# Microcontroller.net
KiCad netlist of a schematic drawn in Altium Designer
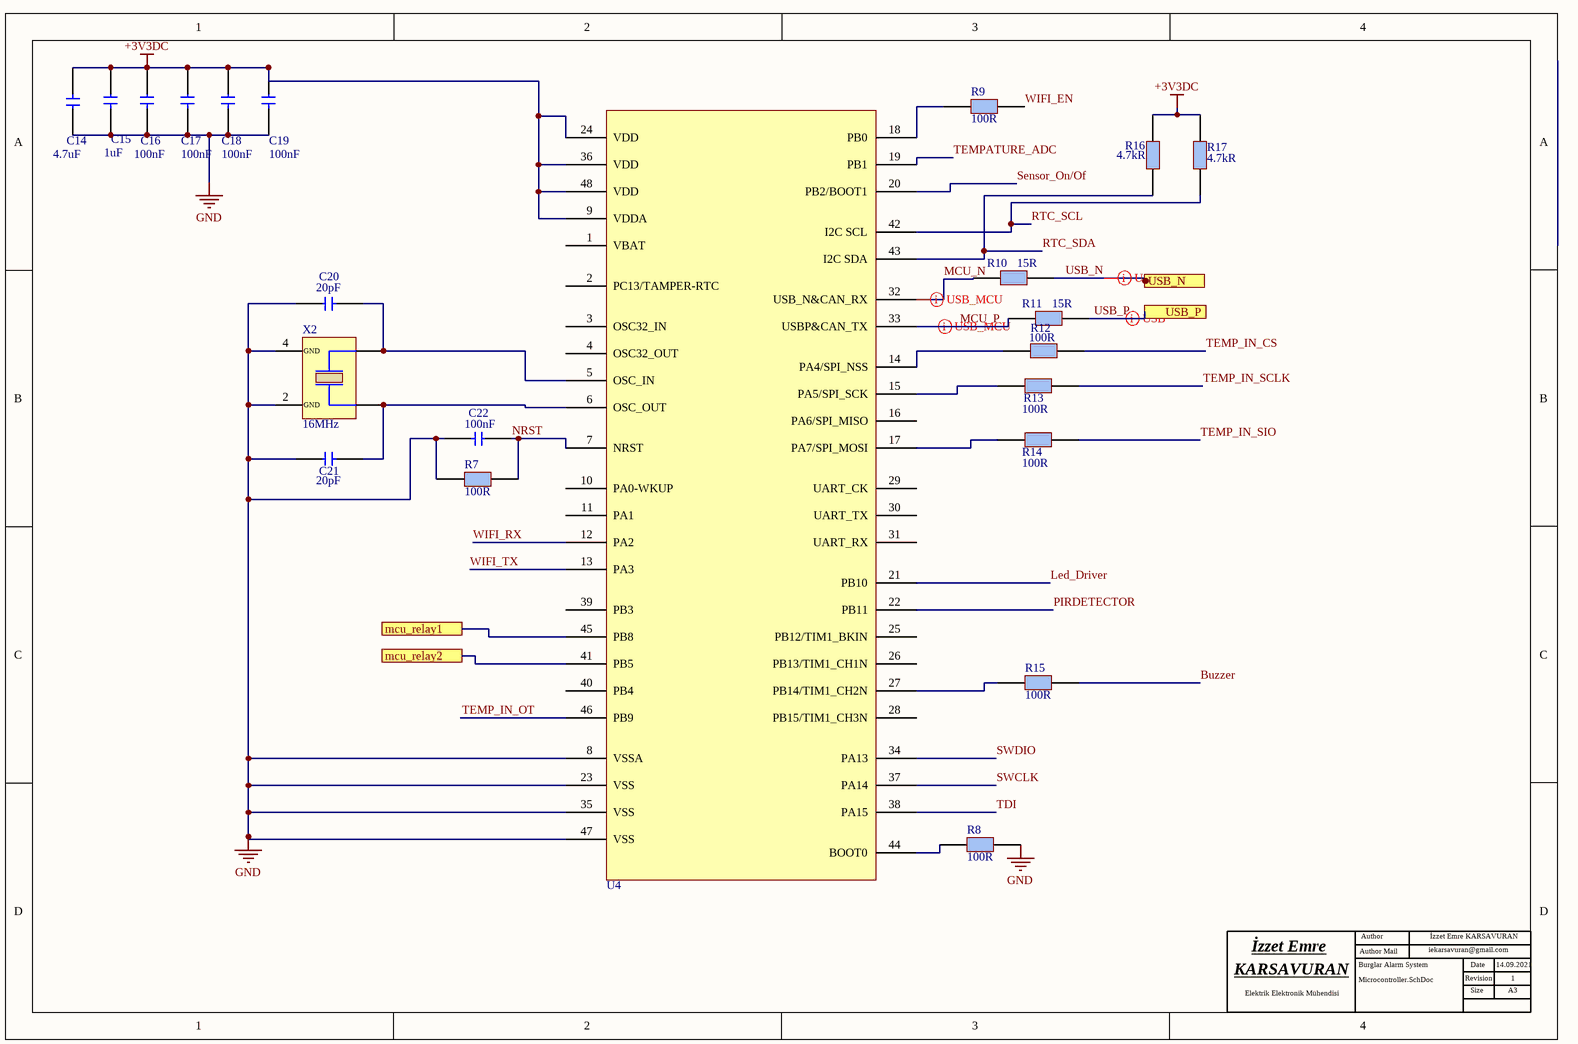
[diagram p0: Microcontroller.SchDoc]

(export (version "E")
  (design (tool "Eeschema 10.0.6"))
  (components
    (comp (ref "C14")
      (value "CL21A475KAQNNNE")
      (footprint "CAP_0805")
      (fields
        (field (name "MANUFACTURER") "Samsung")
        (field (name "TOLERANCE") "10%")
        (field (name "CAPACITANCE") "4.7uF")
        (field (name "DESIGNED BY") "İzzet Emre KARSAVURAN")
      )
      (libsource (lib "burglar_alarm_system_Library") (part "CAP CER 4.7uF"))
    )
    (comp (ref "C15")
      (value "CL21B105KBFNNNE")
      (footprint "CAP_0805")
      (fields
        (field (name "MANUFACTURER") "Samsung")
        (field (name "TOLERANCE") "10%")
        (field (name "VOLTAGE") "50V")
        (field (name "CAPACITANCE") "1uF")
        (field (name "DESIGNED BY") "İzzet Emre KARSAVURAN")
      )
      (libsource (lib "burglar_alarm_system_Library") (part "CAP CER 1uF"))
    )
    (comp (ref "C16")
      (value "CL21B104KBCNNNC")
      (footprint "CAP_0805")
      (fields
        (field (name "MANUFACTURER") "Samsung")
        (field (name "TOLERANCE") "10%")
        (field (name "VOLTAGE") "50V")
        (field (name "CAPACITANCE") "100nF")
        (field (name "DESIGNED BY") "İzzet Emre KARSAVURAN")
      )
      (libsource (lib "burglar_alarm_system_Library") (part "CAP CER 100nF-0803"))
    )
    (comp (ref "C17")
      (value "CL21B104KBCNNNC")
      (footprint "CAP_0805")
      (fields
        (field (name "MANUFACTURER") "Samsung")
        (field (name "TOLERANCE") "10%")
        (field (name "VOLTAGE") "50V")
        (field (name "CAPACITANCE") "100nF")
        (field (name "DESIGNED BY") "İzzet Emre KARSAVURAN")
      )
      (libsource (lib "burglar_alarm_system_Library") (part "CAP CER 100nF-0803"))
    )
    (comp (ref "C18")
      (value "CL21B104KBCNNNC")
      (footprint "CAP_0805")
      (fields
        (field (name "MANUFACTURER") "Samsung")
        (field (name "TOLERANCE") "10%")
        (field (name "VOLTAGE") "50V")
        (field (name "CAPACITANCE") "100nF")
        (field (name "DESIGNED BY") "İzzet Emre KARSAVURAN")
      )
      (libsource (lib "burglar_alarm_system_Library") (part "CAP CER 100nF-0803"))
    )
    (comp (ref "C19")
      (value "CL21B104KBCNNNC")
      (footprint "CAP_0805")
      (fields
        (field (name "MANUFACTURER") "Samsung")
        (field (name "TOLERANCE") "10%")
        (field (name "VOLTAGE") "50V")
        (field (name "CAPACITANCE") "100nF")
        (field (name "DESIGNED BY") "İzzet Emre KARSAVURAN")
      )
      (libsource (lib "burglar_alarm_system_Library") (part "CAP CER 100nF-0803"))
    )
    (comp (ref "C20")
      (value "CL10C200JB8NNNC")
      (footprint "CAP_0603")
      (fields
        (field (name "MANUFACTURER") "Samsung")
        (field (name "TOLERANCE") "5%")
        (field (name "VOLTAGE") "50V")
        (field (name "CAPACITANCE") "20pF")
        (field (name "DESIGNED BY") "İzzet Emre Karsavuran")
      )
      (libsource (lib "burglar_alarm_system_Library") (part "CAP CER 20pF"))
    )
    (comp (ref "C21")
      (value "CL10C200JB8NNNC")
      (footprint "CAP_0603")
      (fields
        (field (name "MANUFACTURER") "Samsung")
        (field (name "TOLERANCE") "5%")
        (field (name "VOLTAGE") "50V")
        (field (name "CAPACITANCE") "20pF")
        (field (name "DESIGNED BY") "İzzet Emre Karsavuran")
      )
      (libsource (lib "burglar_alarm_system_Library") (part "CAP CER 20pF"))
    )
    (comp (ref "C22")
      (value "CL21B104KBCNNNC")
      (footprint "CAP_0805")
      (fields
        (field (name "MANUFACTURER") "Samsung")
        (field (name "TOLERANCE") "10%")
        (field (name "VOLTAGE") "50V")
        (field (name "CAPACITANCE") "100nF")
        (field (name "DESIGNED BY") "İzzet Emre KARSAVURAN")
      )
      (libsource (lib "burglar_alarm_system_Library") (part "CAP CER 100nF-0803"))
    )
    (comp (ref "R7")
      (value "RC0603JR-07100RL")
      (footprint "RES_0603")
      (description "Res Thick Film 0603 100 Ohm 5% 0.1W(1/10W) ±100ppm/C Molded SMD Paper T/R")
      (fields
        (field (name "MANUFACTURER") "Yageo")
        (field (name "TOLERANCE") "5%")
        (field (name "RESISTANCE") "100R")
        (field (name "DESIGNED BY") "İzzet Emre KARSAVURAN")
      )
      (libsource (lib "burglar_alarm_system_Library") (part "RES 100 OHM"))
    )
    (comp (ref "R8")
      (value "RC0603JR-07100RL")
      (footprint "RES_0603")
      (description "Res Thick Film 0603 100 Ohm 5% 0.1W(1/10W) ±100ppm/C Molded SMD Paper T/R")
      (fields
        (field (name "MANUFACTURER") "Yageo")
        (field (name "TOLERANCE") "5%")
        (field (name "RESISTANCE") "100R")
        (field (name "DESIGNED BY") "İzzet Emre KARSAVURAN")
      )
      (libsource (lib "burglar_alarm_system_Library") (part "RES 100 OHM"))
    )
    (comp (ref "R9")
      (value "RC0603JR-07100RL")
      (footprint "RES_0603")
      (description "Res Thick Film 0603 100 Ohm 5% 0.1W(1/10W) ±100ppm/C Molded SMD Paper T/R")
      (fields
        (field (name "MANUFACTURER") "Yageo")
        (field (name "TOLERANCE") "5%")
        (field (name "RESISTANCE") "100R")
        (field (name "DESIGNED BY") "İzzet Emre KARSAVURAN")
      )
      (libsource (lib "burglar_alarm_system_Library") (part "RES 100 OHM"))
    )
    (comp (ref "R10")
      (value "RC0603JR-0715RL")
      (footprint "RES_0603")
      (fields
        (field (name "MANUFACTURER") "Yageo")
        (field (name "TOLERANCE") "5%")
        (field (name "RESISTANCE") "15R")
        (field (name "DESIGNED BY") "İzzet Emre KARSAVURAN")
      )
      (libsource (lib "burglar_alarm_system_Library") (part "RES 15 OHM"))
    )
    (comp (ref "R11")
      (value "RC0603JR-0715RL")
      (footprint "RES_0603")
      (fields
        (field (name "MANUFACTURER") "Yageo")
        (field (name "TOLERANCE") "5%")
        (field (name "RESISTANCE") "15R")
        (field (name "DESIGNED BY") "İzzet Emre KARSAVURAN")
      )
      (libsource (lib "burglar_alarm_system_Library") (part "RES 15 OHM"))
    )
    (comp (ref "R12")
      (value "RC0603JR-07100RL")
      (footprint "RES_0603")
      (description "Res Thick Film 0603 100 Ohm 5% 0.1W(1/10W) ±100ppm/C Molded SMD Paper T/R")
      (fields
        (field (name "MANUFACTURER") "Yageo")
        (field (name "TOLERANCE") "5%")
        (field (name "RESISTANCE") "100R")
        (field (name "DESIGNED BY") "İzzet Emre KARSAVURAN")
      )
      (libsource (lib "burglar_alarm_system_Library") (part "RES 100 OHM"))
    )
    (comp (ref "R13")
      (value "RC0603JR-07100RL")
      (footprint "RES_0603")
      (description "Res Thick Film 0603 100 Ohm 5% 0.1W(1/10W) ±100ppm/C Molded SMD Paper T/R")
      (fields
        (field (name "MANUFACTURER") "Yageo")
        (field (name "TOLERANCE") "5%")
        (field (name "RESISTANCE") "100R")
        (field (name "DESIGNED BY") "İzzet Emre KARSAVURAN")
      )
      (libsource (lib "burglar_alarm_system_Library") (part "RES 100 OHM"))
    )
    (comp (ref "R14")
      (value "RC0603JR-07100RL")
      (footprint "RES_0603")
      (description "Res Thick Film 0603 100 Ohm 5% 0.1W(1/10W) ±100ppm/C Molded SMD Paper T/R")
      (fields
        (field (name "MANUFACTURER") "Yageo")
        (field (name "TOLERANCE") "5%")
        (field (name "RESISTANCE") "100R")
        (field (name "DESIGNED BY") "İzzet Emre KARSAVURAN")
      )
      (libsource (lib "burglar_alarm_system_Library") (part "RES 100 OHM"))
    )
    (comp (ref "R15")
      (value "RC0603JR-07100RL")
      (footprint "RES_0603")
      (description "Res Thick Film 0603 100 Ohm 5% 0.1W(1/10W) ±100ppm/C Molded SMD Paper T/R")
      (fields
        (field (name "MANUFACTURER") "Yageo")
        (field (name "TOLERANCE") "5%")
        (field (name "RESISTANCE") "100R")
        (field (name "DESIGNED BY") "İzzet Emre KARSAVURAN")
      )
      (libsource (lib "burglar_alarm_system_Library") (part "RES 100 OHM"))
    )
    (comp (ref "R16")
      (value "RC0603JR-074K7L")
      (footprint "RES_0603")
      (description "Res Thick Film 0603 4.7K Ohm 5% 0.1W(1/10W) ±100ppm/C Molded SMD Paper T/R")
      (fields
        (field (name "MANUFACTURER") "Yageo")
        (field (name "TOLERANCE") "5%")
        (field (name "RESISTANCE") "4.7kR")
        (field (name "DESIGNED BY") "İzzet Emre KARSAVURAN")
      )
      (libsource (lib "burglar_alarm_system_Library") (part "RES 47k OHM"))
    )
    (comp (ref "R17")
      (value "RC0603JR-074K7L")
      (footprint "RES_0603")
      (description "Res Thick Film 0603 4.7K Ohm 5% 0.1W(1/10W) ±100ppm/C Molded SMD Paper T/R")
      (fields
        (field (name "MANUFACTURER") "Yageo")
        (field (name "TOLERANCE") "5%")
        (field (name "RESISTANCE") "4.7kR")
        (field (name "DESIGNED BY") "İzzet Emre KARSAVURAN")
      )
      (libsource (lib "burglar_alarm_system_Library") (part "RES 47k OHM"))
    )
    (comp (ref "U4")
      (value "STM32F103C6T6A")
      (footprint "LQFP48")
      (description "MCU 32-bit STM32F ARM Cortex M3 RISC 32KB Flash 2.5V/3.3V 48-Pin LQFP Tray")
      (fields
        (field (name "MANUFACTURER") "STMicroelectronics")
        (field (name "DESIGNED BY") "İzzet Emre KARSAVURAN")
      )
      (libsource (lib "burglar_alarm_system_Library") (part "STM32F103C6T6A"))
    )
    (comp (ref "X2")
      (value "ECS-160-20-30B-TR")
      (footprint "ECS")
      (description "CRYSTAL 16.0000MHZ 20PF SMD")
      (fields
        (field (name "MANUFACTURER") "ECS International")
        (field (name "TOLERANCE") "50ppm")
        (field (name "FREQUENCY") "16MHz")
        (field (name "DESIGNED BY") "İzzet Emre KARSAVURAN")
      )
      (libsource (lib "burglar_alarm_system_Library") (part "CRYSTAL 16MHz"))
    )
  )
  (nets
    (net (code "1") (name "+3V3DC") (class "Default")
      (node (ref "C14") (pin "2") (pinfunction "2_2") (pintype "passive"))
      (node (ref "C15") (pin "1") (pinfunction "1_1") (pintype "passive"))
      (node (ref "C16") (pin "1") (pinfunction "1_1") (pintype "passive"))
      (node (ref "C17") (pin "1") (pinfunction "1_1") (pintype "passive"))
      (node (ref "C18") (pin "1") (pinfunction "1_1") (pintype "passive"))
      (node (ref "C19") (pin "1") (pinfunction "1_1") (pintype "passive"))
      (node (ref "R16") (pin "2") (pinfunction "2_2") (pintype "passive"))
      (node (ref "R17") (pin "2") (pinfunction "2_2") (pintype "passive"))
      (node (ref "U4") (pin "24") (pinfunction "VDD_24") (pintype "passive"))
      (node (ref "U4") (pin "36") (pinfunction "VDD_36") (pintype "passive"))
      (node (ref "U4") (pin "48") (pinfunction "VDD_48") (pintype "passive"))
      (node (ref "U4") (pin "9") (pinfunction "VDDA_9") (pintype "passive"))
    )
    (net (code "2") (name "/Buzzer") (class "Default")
      (node (ref "R15") (pin "1") (pinfunction "1_1") (pintype "passive"))
    )
    (net (code "3") (name "/Led_Driver") (class "Default")
      (node (ref "U4") (pin "21") (pinfunction "PB10_21") (pintype "passive"))
    )
    (net (code "4") (name "/MCU_N") (class "Default")
      (node (ref "R10") (pin "1") (pinfunction "1_1") (pintype "passive"))
      (node (ref "U4") (pin "32") (pinfunction "USB_N&CAN_RX_32") (pintype "passive"))
    )
    (net (code "5") (name "/MCU_P") (class "Default")
      (node (ref "R11") (pin "1") (pinfunction "1_1") (pintype "passive"))
      (node (ref "U4") (pin "33") (pinfunction "USBP&CAN_TX_33") (pintype "passive"))
    )
    (net (code "6") (name "/NRST") (class "Default")
      (node (ref "C22") (pin "1") (pinfunction "1_1") (pintype "passive"))
      (node (ref "R7") (pin "1") (pinfunction "1_1") (pintype "passive"))
      (node (ref "U4") (pin "7") (pinfunction "NRST_7") (pintype "passive"))
    )
    (net (code "7") (name "/PIRDETECTOR") (class "Default")
      (node (ref "U4") (pin "22") (pinfunction "PB11_22") (pintype "passive"))
    )
    (net (code "8") (name "/RTC_SCL") (class "Default")
      (node (ref "R17") (pin "1") (pinfunction "1_1") (pintype "passive"))
      (node (ref "U4") (pin "42") (pinfunction "I2C_SCL_42") (pintype "passive"))
    )
    (net (code "9") (name "/RTC_SDA") (class "Default")
      (node (ref "R16") (pin "1") (pinfunction "1_1") (pintype "passive"))
      (node (ref "U4") (pin "43") (pinfunction "I2C_SDA_43") (pintype "passive"))
    )
    (net (code "10") (name "/SWCLK") (class "Default")
      (node (ref "U4") (pin "37") (pinfunction "PA14_37") (pintype "passive"))
    )
    (net (code "11") (name "/SWDIO") (class "Default")
      (node (ref "U4") (pin "34") (pinfunction "PA13_34") (pintype "passive"))
    )
    (net (code "12") (name "/Sensor_On{slash}Of") (class "Default")
      (node (ref "U4") (pin "20") (pinfunction "PB2/BOOT1_20") (pintype "passive"))
    )
    (net (code "13") (name "/TDI") (class "Default")
      (node (ref "U4") (pin "38") (pinfunction "PA15_38") (pintype "passive"))
    )
    (net (code "14") (name "/TEMPATURE_ADC") (class "Default")
      (node (ref "U4") (pin "19") (pinfunction "PB1_19") (pintype "passive"))
    )
    (net (code "15") (name "/TEMP_IN_CS") (class "Default")
      (node (ref "R12") (pin "1") (pinfunction "1_1") (pintype "passive"))
    )
    (net (code "16") (name "/TEMP_IN_OT") (class "Default")
      (node (ref "U4") (pin "46") (pinfunction "PB9_46") (pintype "passive"))
    )
    (net (code "17") (name "/TEMP_IN_SCLK") (class "Default")
      (node (ref "R13") (pin "1") (pinfunction "1_1") (pintype "passive"))
    )
    (net (code "18") (name "/TEMP_IN_SIO") (class "Default")
      (node (ref "R14") (pin "1") (pinfunction "1_1") (pintype "passive"))
    )
    (net (code "19") (name "/USB_N") (class "Default")
      (node (ref "R10") (pin "2") (pinfunction "2_2") (pintype "passive"))
    )
    (net (code "20") (name "/USB_P") (class "Default")
      (node (ref "R11") (pin "2") (pinfunction "2_2") (pintype "passive"))
    )
    (net (code "21") (name "/WIFI_EN") (class "Default")
      (node (ref "R9") (pin "1") (pinfunction "1_1") (pintype "passive"))
    )
    (net (code "22") (name "/WIFI_RX") (class "Default")
      (node (ref "U4") (pin "12") (pinfunction "PA2_12") (pintype "passive"))
    )
    (net (code "23") (name "/WIFI_TX") (class "Default")
      (node (ref "U4") (pin "13") (pinfunction "PA3_13") (pintype "passive"))
    )
    (net (code "24") (name "/mcu_relay1") (class "Default")
      (node (ref "U4") (pin "45") (pinfunction "PB8_45") (pintype "passive"))
    )
    (net (code "25") (name "/mcu_relay2") (class "Default")
      (node (ref "U4") (pin "41") (pinfunction "PB5_41") (pintype "passive"))
    )
    (net (code "26") (name "GND") (class "Default")
      (node (ref "C14") (pin "1") (pinfunction "1_1") (pintype "passive"))
      (node (ref "C15") (pin "2") (pinfunction "2_2") (pintype "passive"))
      (node (ref "C16") (pin "2") (pinfunction "2_2") (pintype "passive"))
      (node (ref "C17") (pin "2") (pinfunction "2_2") (pintype "passive"))
      (node (ref "C18") (pin "2") (pinfunction "2_2") (pintype "passive"))
      (node (ref "C19") (pin "2") (pinfunction "2_2") (pintype "passive"))
      (node (ref "C20") (pin "1") (pinfunction "1_1") (pintype "passive"))
      (node (ref "C21") (pin "1") (pinfunction "1_1") (pintype "passive"))
      (node (ref "C22") (pin "2") (pinfunction "2_2") (pintype "passive"))
      (node (ref "R7") (pin "2") (pinfunction "2_2") (pintype "passive"))
      (node (ref "R8") (pin "1") (pinfunction "1_1") (pintype "passive"))
      (node (ref "U4") (pin "23") (pinfunction "VSS_23") (pintype "passive"))
      (node (ref "U4") (pin "35") (pinfunction "VSS_35") (pintype "passive"))
      (node (ref "U4") (pin "47") (pinfunction "VSS_47") (pintype "passive"))
      (node (ref "U4") (pin "8") (pinfunction "VSSA_8") (pintype "passive"))
      (node (ref "X2") (pin "2") (pinfunction "GND_2") (pintype "passive"))
      (node (ref "X2") (pin "4") (pinfunction "GND_4") (pintype "passive"))
    )
    (net (code "27") (name "Net-(U4-BOOT0)") (class "Default")
      (node (ref "R8") (pin "2") (pinfunction "2_2") (pintype "passive"))
      (node (ref "U4") (pin "44") (pinfunction "BOOT0_44") (pintype "passive"))
    )
    (net (code "28") (name "Net-(U4-OSC_IN)") (class "Default")
      (node (ref "C20") (pin "2") (pinfunction "2_2") (pintype "passive"))
      (node (ref "U4") (pin "5") (pinfunction "OSC_IN_5") (pintype "passive"))
      (node (ref "X2") (pin "3") (pinfunction "3_3") (pintype "passive"))
    )
    (net (code "29") (name "Net-(U4-OSC_OUT)") (class "Default")
      (node (ref "C21") (pin "2") (pinfunction "2_2") (pintype "passive"))
      (node (ref "U4") (pin "6") (pinfunction "OSC_OUT_6") (pintype "passive"))
      (node (ref "X2") (pin "1") (pinfunction "1_1") (pintype "passive"))
    )
    (net (code "30") (name "Net-(U4-PA4{slash}SPI_NSS)") (class "Default")
      (node (ref "R12") (pin "2") (pinfunction "2_2") (pintype "passive"))
      (node (ref "U4") (pin "14") (pinfunction "PA4/SPI_NSS_14") (pintype "passive"))
    )
    (net (code "31") (name "Net-(U4-PA5{slash}SPI_SCK)") (class "Default")
      (node (ref "R13") (pin "2") (pinfunction "2_2") (pintype "passive"))
      (node (ref "U4") (pin "15") (pinfunction "PA5/SPI_SCK_15") (pintype "passive"))
    )
    (net (code "32") (name "Net-(U4-PA7{slash}SPI_MOSI)") (class "Default")
      (node (ref "R14") (pin "2") (pinfunction "2_2") (pintype "passive"))
      (node (ref "U4") (pin "17") (pinfunction "PA7/SPI_MOSI_17") (pintype "passive"))
    )
    (net (code "33") (name "Net-(U4-PB0)") (class "Default")
      (node (ref "R9") (pin "2") (pinfunction "2_2") (pintype "passive"))
      (node (ref "U4") (pin "18") (pinfunction "PB0_18") (pintype "passive"))
    )
    (net (code "34") (name "Net-(U4-PB14{slash}TIM1_CH2N)") (class "Default")
      (node (ref "R15") (pin "2") (pinfunction "2_2") (pintype "passive"))
      (node (ref "U4") (pin "27") (pinfunction "PB14/TIM1_CH2N_27") (pintype "passive"))
    )
    (net (code "35") (name "unconnected-(U4-OSC32_IN-Pad3)") (class "Default")
      (node (ref "U4") (pin "3") (pinfunction "OSC32_IN_3") (pintype "passive"))
    )
    (net (code "36") (name "unconnected-(U4-OSC32_OUT-Pad4)") (class "Default")
      (node (ref "U4") (pin "4") (pinfunction "OSC32_OUT_4") (pintype "passive"))
    )
    (net (code "37") (name "unconnected-(U4-PA0-WKUP-Pad10)") (class "Default")
      (node (ref "U4") (pin "10") (pinfunction "PA0-WKUP_10") (pintype "passive"))
    )
    (net (code "38") (name "unconnected-(U4-PA1-Pad11)") (class "Default")
      (node (ref "U4") (pin "11") (pinfunction "PA1_11") (pintype "passive"))
    )
    (net (code "39") (name "unconnected-(U4-PA6{slash}SPI_MISO-Pad16)") (class "Default")
      (node (ref "U4") (pin "16") (pinfunction "PA6/SPI_MISO_16") (pintype "passive"))
    )
    (net (code "40") (name "unconnected-(U4-PB3-Pad39)") (class "Default")
      (node (ref "U4") (pin "39") (pinfunction "PB3_39") (pintype "passive"))
    )
    (net (code "41") (name "unconnected-(U4-PB4-Pad40)") (class "Default")
      (node (ref "U4") (pin "40") (pinfunction "PB4_40") (pintype "passive"))
    )
    (net (code "42") (name "unconnected-(U4-PB12{slash}TIM1_BKIN-Pad25)") (class "Default")
      (node (ref "U4") (pin "25") (pinfunction "PB12/TIM1_BKIN_25") (pintype "passive"))
    )
    (net (code "43") (name "unconnected-(U4-PB13{slash}TIM1_CH1N-Pad26)") (class "Default")
      (node (ref "U4") (pin "26") (pinfunction "PB13/TIM1_CH1N_26") (pintype "passive"))
    )
    (net (code "44") (name "unconnected-(U4-PB15{slash}TIM1_CH3N-Pad28)") (class "Default")
      (node (ref "U4") (pin "28") (pinfunction "PB15/TIM1_CH3N_28") (pintype "passive"))
    )
    (net (code "45") (name "unconnected-(U4-PC13{slash}TAMPER-RTC-Pad2)") (class "Default")
      (node (ref "U4") (pin "2") (pinfunction "PC13/TAMPER-RTC_2") (pintype "passive"))
    )
    (net (code "46") (name "unconnected-(U4-UART_CK-Pad29)") (class "Default")
      (node (ref "U4") (pin "29") (pinfunction "UART_CK_29") (pintype "passive"))
    )
    (net (code "47") (name "unconnected-(U4-UART_RX-Pad31)") (class "Default")
      (node (ref "U4") (pin "31") (pinfunction "UART_RX_31") (pintype "passive"))
    )
    (net (code "48") (name "unconnected-(U4-UART_TX-Pad30)") (class "Default")
      (node (ref "U4") (pin "30") (pinfunction "UART_TX_30") (pintype "passive"))
    )
    (net (code "49") (name "unconnected-(U4-VBAT-Pad1)") (class "Default")
      (node (ref "U4") (pin "1") (pinfunction "VBAT_1") (pintype "passive"))
    )
  )
)
